# SCHEMATIC_INKTIME.net
KiCad netlist of a schematic drawn in EAGLE
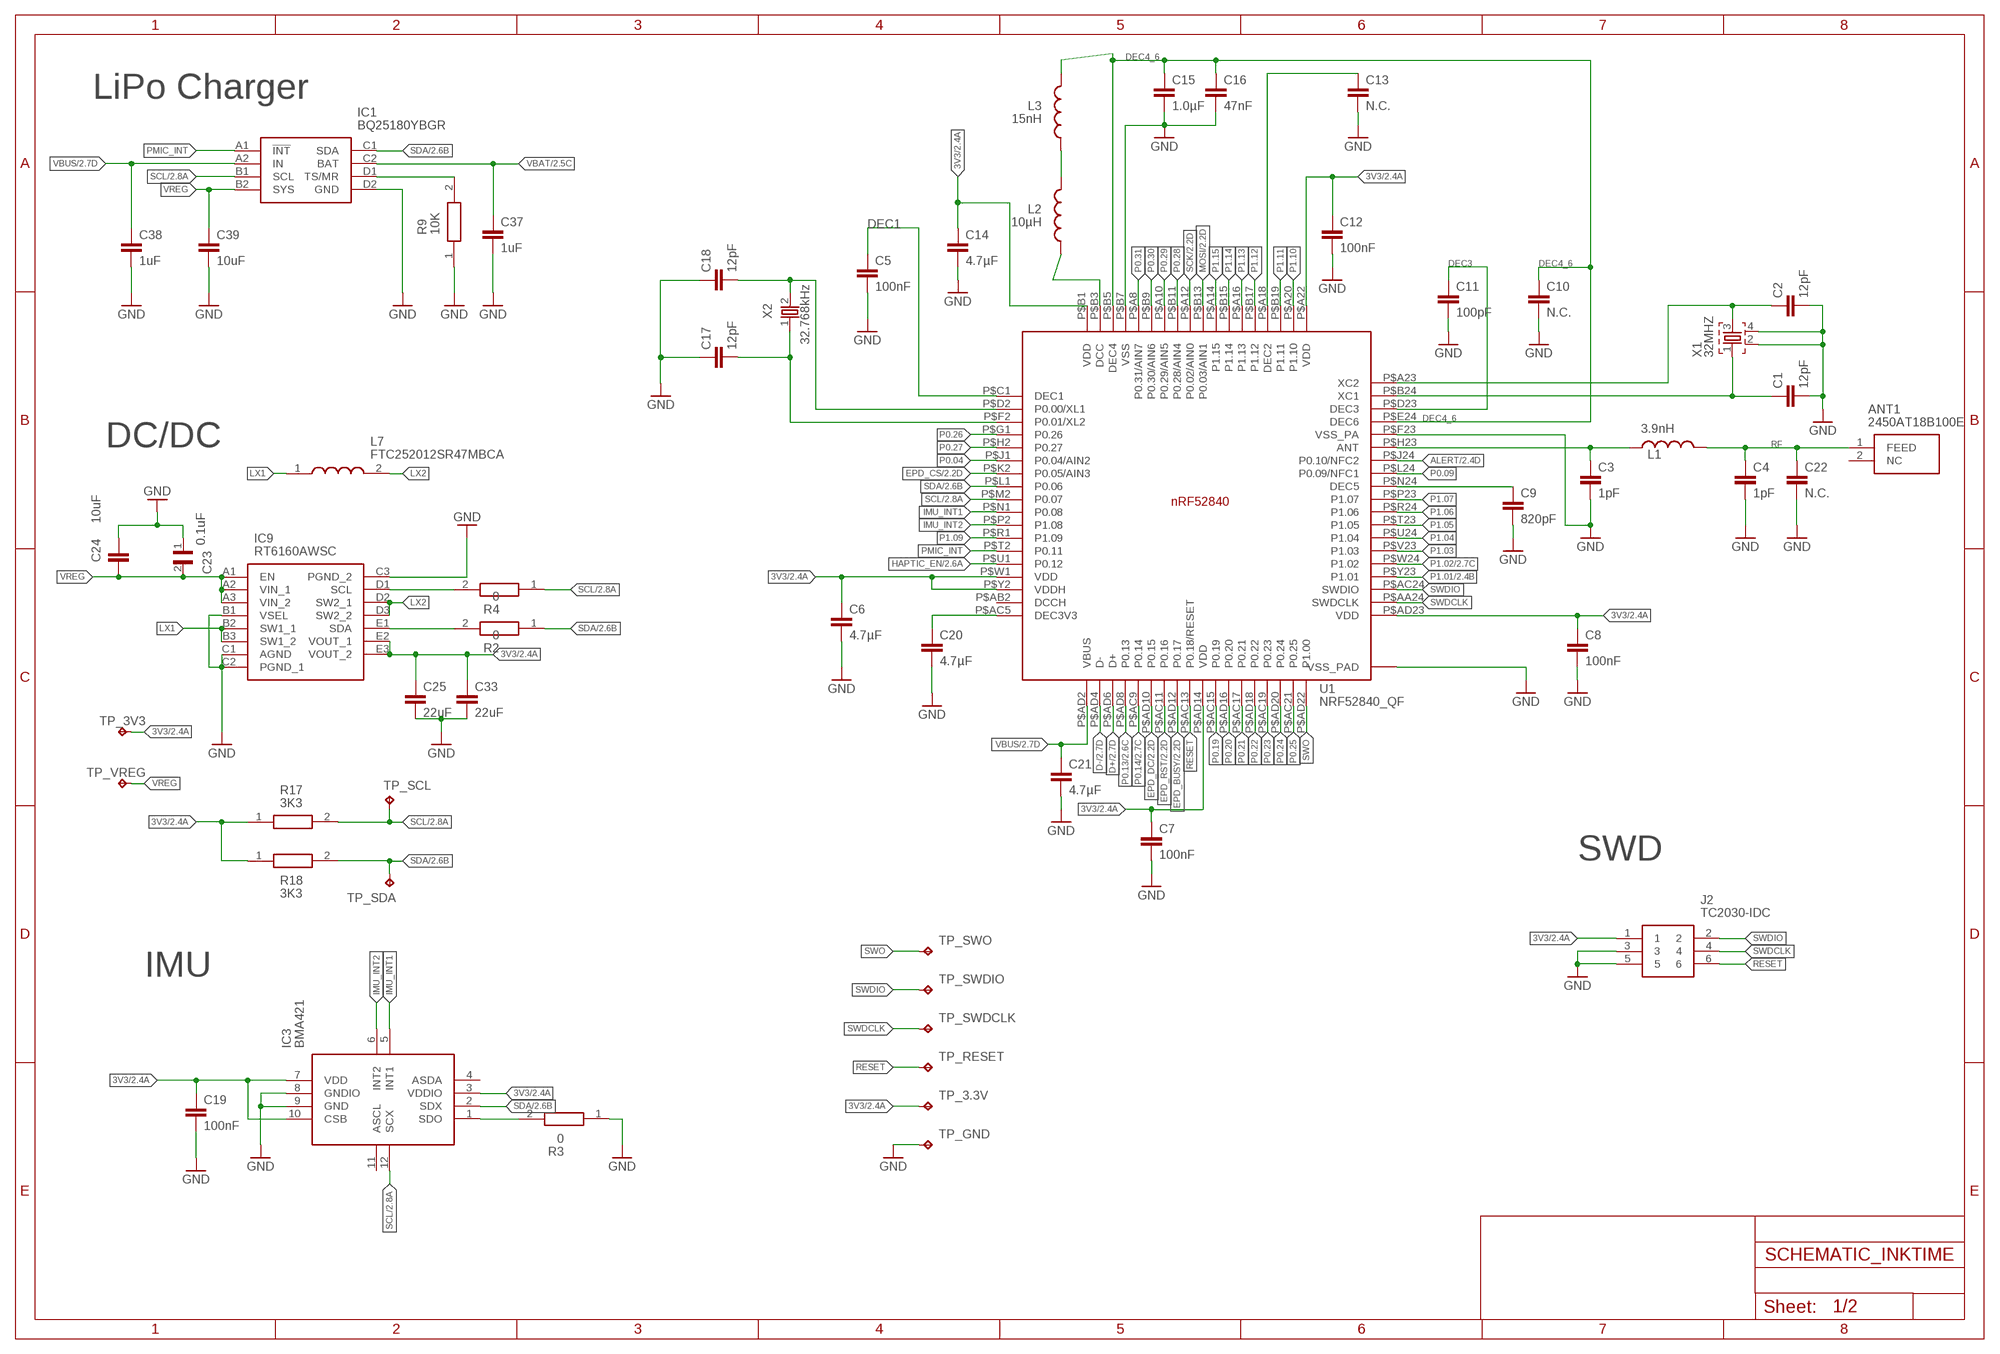
[diagram p0: schematic, sheet 1]
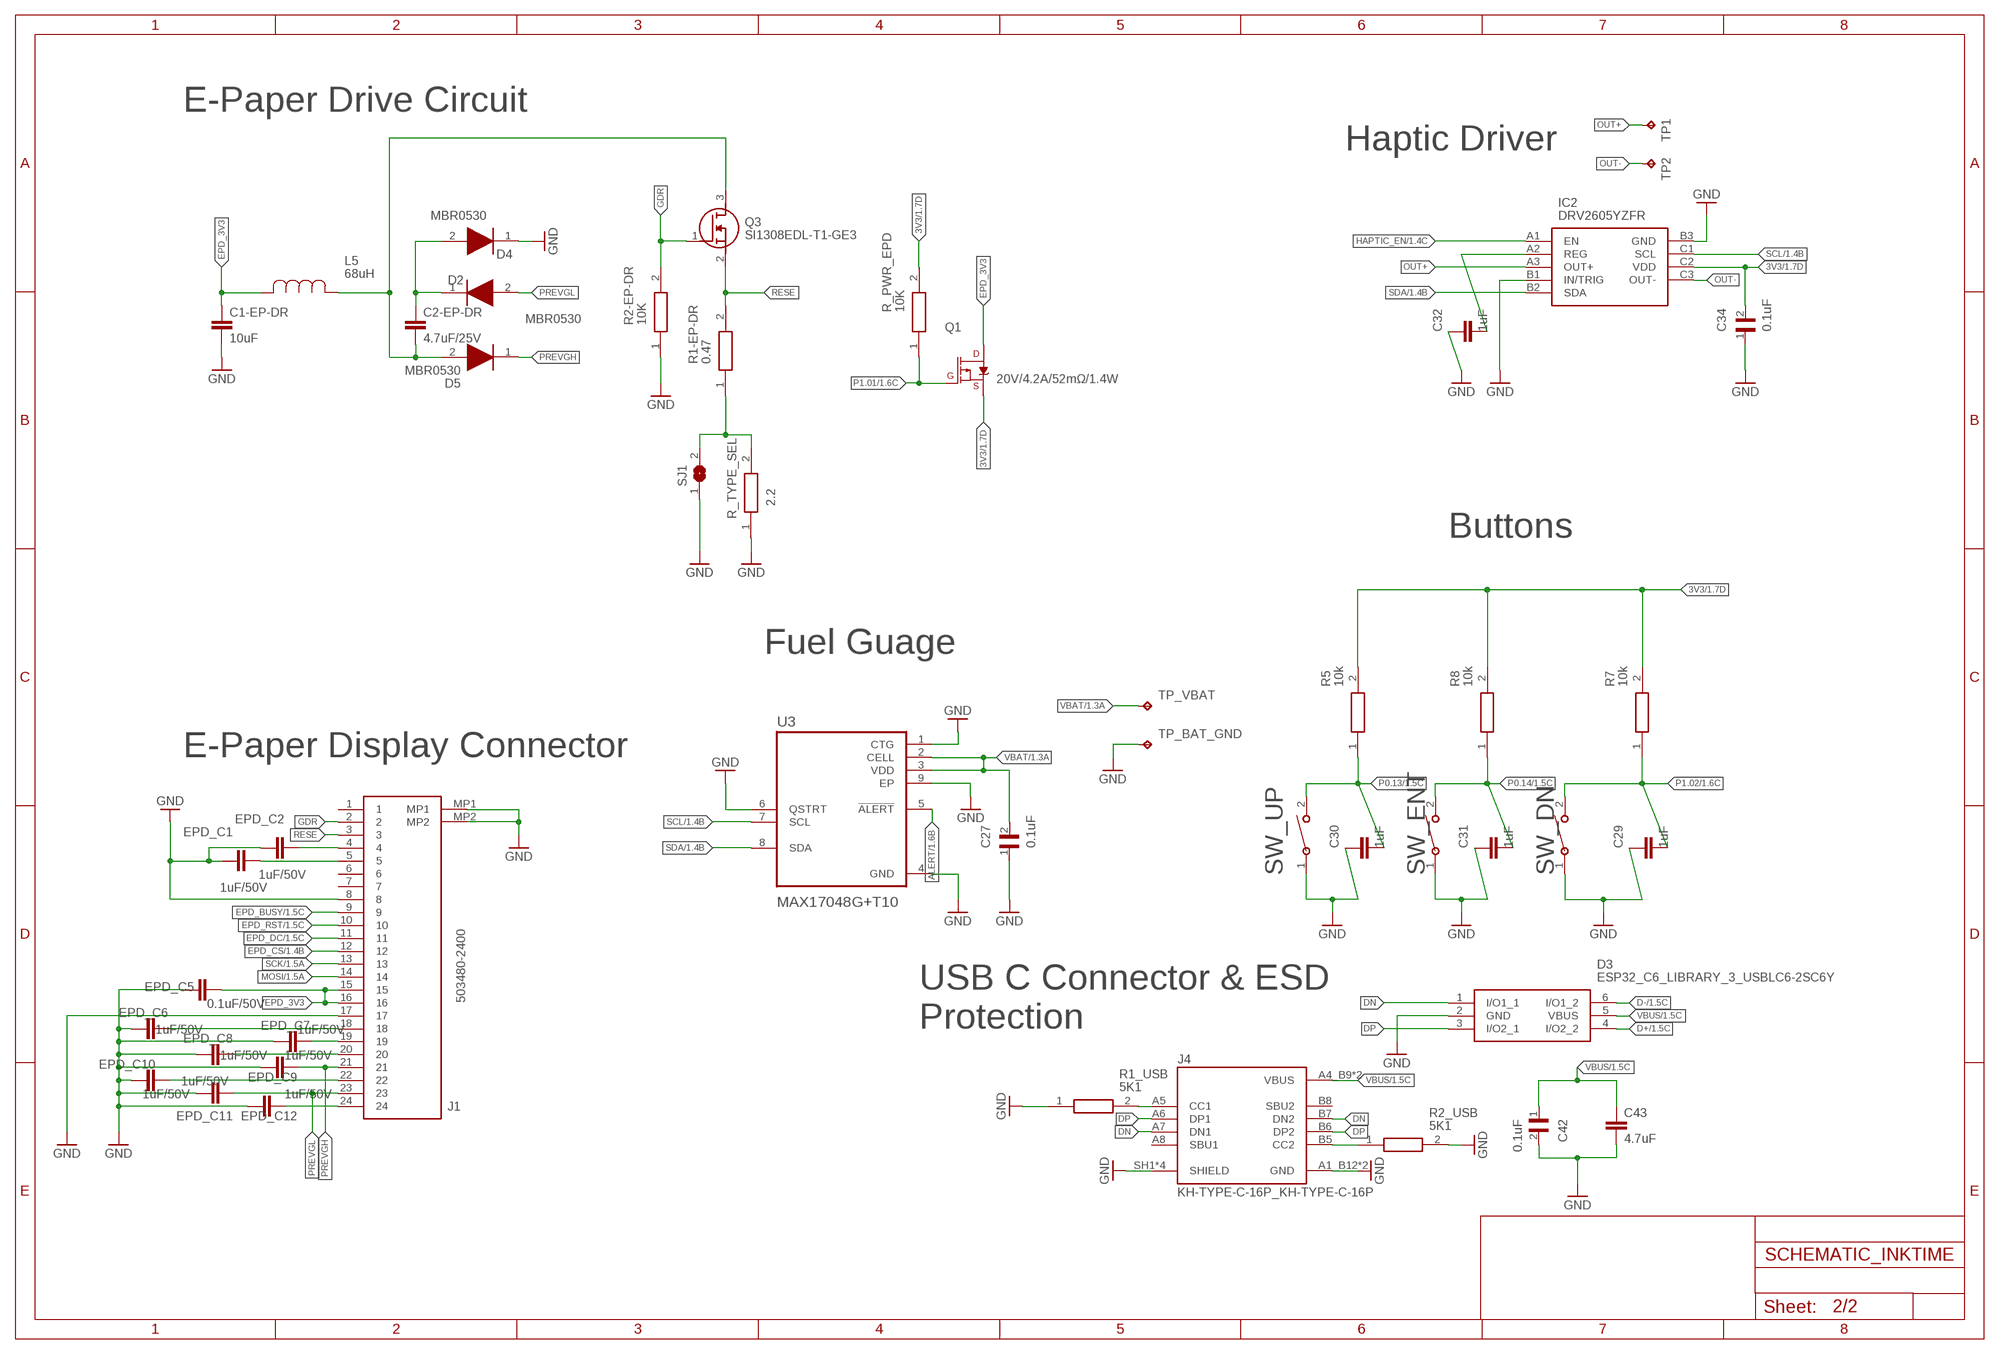
[diagram p1: schematic, sheet 2]

(export (version "E")
  (design (tool "Eeschema 10.0.6"))
  (components
    (comp (ref "ANT1")
      (value "2450AT18B100E")
      (footprint "eagle-import:2450AT18B100E_ANTC3216X140N")
      (fields (field (name "MOUSER_PART_NUMBER") "609-2450AT18B100E"))
      (libsource (lib "eagle-import") (part "2450AT18B100E_2450AT18B100E"))
    )
    (comp (ref "C1")
      (value "12pF")
      (footprint "eagle-import:NORDIC_NRF_3_RESC0201_L")
      (libsource (lib "eagle-import") (part "NORDIC_NRF_3_CAPACITOR_0201_L"))
    )
    (comp (ref "C2")
      (value "12pF")
      (footprint "eagle-import:NORDIC_NRF_3_RESC0201_L")
      (libsource (lib "eagle-import") (part "NORDIC_NRF_3_CAPACITOR_0201_L"))
    )
    (comp (ref "C3")
      (value "1pF")
      (footprint "eagle-import:NORDIC_NRF_3_RESC0201_L")
      (libsource (lib "eagle-import") (part "NORDIC_NRF_3_CAPACITOR_0201_L"))
    )
    (comp (ref "C4")
      (value "1pF")
      (footprint "eagle-import:NORDIC_NRF_3_RESC0201_L")
      (libsource (lib "eagle-import") (part "NORDIC_NRF_3_CAPACITOR_0201_L"))
    )
    (comp (ref "C5")
      (value "100nF")
      (footprint "eagle-import:NORDIC_NRF_3_RESC0201_L")
      (libsource (lib "eagle-import") (part "NORDIC_NRF_3_CAPACITOR_0201_L"))
    )
    (comp (ref "C6")
      (value "4.7µF")
      (footprint "eagle-import:NORDIC_NRF_3_RESC0402_L")
      (libsource (lib "eagle-import") (part "NORDIC_NRF_3_CAPACITOR_0402_L"))
    )
    (comp (ref "C7")
      (value "100nF")
      (footprint "eagle-import:NORDIC_NRF_3_RESC0201_L")
      (libsource (lib "eagle-import") (part "NORDIC_NRF_3_CAPACITOR_0201_L"))
    )
    (comp (ref "C8")
      (value "100nF")
      (footprint "eagle-import:NORDIC_NRF_3_RESC0201_L")
      (libsource (lib "eagle-import") (part "NORDIC_NRF_3_CAPACITOR_0201_L"))
    )
    (comp (ref "C9")
      (value "820pF")
      (footprint "eagle-import:NORDIC_NRF_3_RESC0201_L")
      (libsource (lib "eagle-import") (part "NORDIC_NRF_3_CAPACITOR_0201_L"))
    )
    (comp (ref "C10")
      (value "N.C.")
      (footprint "eagle-import:NORDIC_NRF_3_RESC0201_L")
      (libsource (lib "eagle-import") (part "NORDIC_NRF_3_CAPACITOR_0201_L"))
    )
    (comp (ref "C11")
      (value "100pF")
      (footprint "eagle-import:NORDIC_NRF_3_RESC0201_L")
      (libsource (lib "eagle-import") (part "NORDIC_NRF_3_CAPACITOR_0201_L"))
    )
    (comp (ref "C12")
      (value "100nF")
      (footprint "eagle-import:NORDIC_NRF_3_RESC0201_L")
      (libsource (lib "eagle-import") (part "NORDIC_NRF_3_CAPACITOR_0201_L"))
    )
    (comp (ref "C13")
      (value "N.C.")
      (footprint "eagle-import:NORDIC_NRF_3_RESC0201_L")
      (libsource (lib "eagle-import") (part "NORDIC_NRF_3_CAPACITOR_0201_L"))
    )
    (comp (ref "C14")
      (value "4.7µF")
      (footprint "eagle-import:NORDIC_NRF_3_RESC0402_L")
      (libsource (lib "eagle-import") (part "NORDIC_NRF_3_CAPACITOR_0402_L"))
    )
    (comp (ref "C15")
      (value "1.0µF")
      (footprint "eagle-import:NORDIC_NRF_3_RESC0402_L")
      (libsource (lib "eagle-import") (part "NORDIC_NRF_3_CAPACITOR_0402_L"))
    )
    (comp (ref "C16")
      (value "47nF")
      (footprint "eagle-import:NORDIC_NRF_3_RESC0201_L")
      (libsource (lib "eagle-import") (part "NORDIC_NRF_3_CAPACITOR_0201_L"))
    )
    (comp (ref "C17")
      (value "12pF")
      (footprint "eagle-import:NORDIC_NRF_3_RESC0201_L")
      (libsource (lib "eagle-import") (part "NORDIC_NRF_3_CAPACITOR_0201_L"))
    )
    (comp (ref "C18")
      (value "12pF")
      (footprint "eagle-import:NORDIC_NRF_3_RESC0201_L")
      (libsource (lib "eagle-import") (part "NORDIC_NRF_3_CAPACITOR_0201_L"))
    )
    (comp (ref "C19")
      (value "100nF")
      (footprint "eagle-import:NORDIC_NRF_3_RESC0201_L")
      (libsource (lib "eagle-import") (part "NORDIC_NRF_3_CAPACITOR_0201_L"))
    )
    (comp (ref "C20")
      (value "4.7µF")
      (footprint "eagle-import:NORDIC_NRF_3_RESC0402_L")
      (libsource (lib "eagle-import") (part "NORDIC_NRF_3_CAPACITOR_0402_L"))
    )
    (comp (ref "C21")
      (value "4.7µF")
      (footprint "eagle-import:NORDIC_NRF_3_RESC0402_L")
      (libsource (lib "eagle-import") (part "NORDIC_NRF_3_CAPACITOR_0402_L"))
    )
    (comp (ref "C22")
      (value "N.C.")
      (footprint "eagle-import:NORDIC_NRF_3_RESC0201_L")
      (libsource (lib "eagle-import") (part "NORDIC_NRF_3_CAPACITOR_0201_L"))
    )
    (comp (ref "C23")
      (value "0.1uF")
      (footprint "eagle-import:GRM011R60J152KE01L_2_CAPC0201X13N")
      (fields (field (name "MF") "Murata") (field (name "MP") "GRM011R60J152KE01L"))
      (libsource (lib "eagle-import") (part "GRM011R60J152KE01L_2_GRM011R60J152KE01L"))
    )
    (comp (ref "C24")
      (value "10uF")
      (footprint "eagle-import:NORDIC_NRF_3_RESC0402_L")
      (libsource (lib "eagle-import") (part "NORDIC_NRF_3_CAPACITOR_0402_L"))
    )
    (comp (ref "C25")
      (value "22uF")
      (footprint "eagle-import:NORDIC_NRF_3_RESC0402_L")
      (libsource (lib "eagle-import") (part "NORDIC_NRF_3_CAPACITOR_0402_L"))
    )
    (comp (ref "C33")
      (value "22uF")
      (footprint "eagle-import:NORDIC_NRF_3_RESC0402_L")
      (libsource (lib "eagle-import") (part "NORDIC_NRF_3_CAPACITOR_0402_L"))
    )
    (comp (ref "C37")
      (value "1uF")
      (footprint "eagle-import:NORDIC_NRF_3_RESC0402_L")
      (libsource (lib "eagle-import") (part "NORDIC_NRF_3_CAPACITOR_0402_L"))
    )
    (comp (ref "C38")
      (value "1uF")
      (footprint "eagle-import:NORDIC_NRF_3_RESC0402_L")
      (libsource (lib "eagle-import") (part "NORDIC_NRF_3_CAPACITOR_0402_L"))
    )
    (comp (ref "C39")
      (value "10uF")
      (footprint "eagle-import:NORDIC_NRF_3_RESC0402_L")
      (libsource (lib "eagle-import") (part "NORDIC_NRF_3_CAPACITOR_0402_L"))
    )
    (comp (ref "IC1")
      (value "BQ25180YBGR")
      (footprint "eagle-import:BQ25180YBGR_BGA8C40P2X4_100X155X50")
      (fields (field (name "MOUSER_PART_NUMBER") "595-BQ25180YBGR"))
      (libsource (lib "eagle-import") (part "BQ25180YBGR_BQ25180YBGR"))
    )
    (comp (ref "IC3")
      (value "BMA421")
      (footprint "eagle-import:BMA423_BMA423")
      (fields (field (name "ARROW_PART_NUMBER") "BMA423") (field (name "MOUSER_PART_NUMBER") "262-BMA423"))
      (libsource (lib "eagle-import") (part "BMA423_BMA423"))
    )
    (comp (ref "IC9")
      (value "RT6160AWSC")
      (footprint "eagle-import:RT6160AWSC_BGA15C40P3X5_140X230X60")
      (fields (field (name "MOUSER_PART_NUMBER") "835-RT6160AWSC"))
      (libsource (lib "eagle-import") (part "RT6160AWSC_RT6160AWSC"))
    )
    (comp (ref "J2")
      (value "TC2030-IDC")
      (footprint "eagle-import:TC2030-IDC_TC2030IDC")
      (libsource (lib "eagle-import") (part "TC2030-IDC_TC2030-IDC"))
    )
    (comp (ref "L1")
      (value "3.9nH")
      (footprint "eagle-import:NORDIC_NRF_2_RESC0402_L")
      (libsource (lib "eagle-import") (part "NORDIC_NRF_2_INDUCTOR_0402_L"))
    )
    (comp (ref "L2")
      (value "10µH")
      (footprint "eagle-import:NORDIC_NRF_2_RESC0402_L")
      (libsource (lib "eagle-import") (part "NORDIC_NRF_2_INDUCTOR_0402_L"))
    )
    (comp (ref "L3")
      (value "15nH")
      (footprint "eagle-import:NORDIC_NRF_2_RESC0402_L")
      (libsource (lib "eagle-import") (part "NORDIC_NRF_2_INDUCTOR_0402_L"))
    )
    (comp (ref "L7")
      (value "FTC252012SR47MBCA")
      (footprint "eagle-import:MLP2016SR47MT0S1_INDC2016X100N")
      (libsource (lib "eagle-import") (part "MLP2016SR47MT0S1_FTC252012SR47MBCA"))
    )
    (comp (ref "R2")
      (value "0")
      (footprint "eagle-import:CPF0201D7K68C1_0201")
      (libsource (lib "eagle-import") (part "CPF0201D7K68C1_CPF0201D7K68C1"))
    )
    (comp (ref "R3")
      (value "0")
      (footprint "eagle-import:CPF0201D7K68C1_0201")
      (libsource (lib "eagle-import") (part "CPF0201D7K68C1_CPF0201D7K68C1"))
    )
    (comp (ref "R4")
      (value "0")
      (footprint "eagle-import:CPF0201D7K68C1_0201")
      (libsource (lib "eagle-import") (part "CPF0201D7K68C1_CPF0201D7K68C1"))
    )
    (comp (ref "R9")
      (value "10K")
      (footprint "eagle-import:CPF0201D7K68C1_0201")
      (libsource (lib "eagle-import") (part "CPF0201D7K68C1_CPF0201D7K68C1"))
    )
    (comp (ref "R17")
      (value "3K3")
      (footprint "eagle-import:CPF0201D7K68C1_0201")
      (libsource (lib "eagle-import") (part "CPF0201D7K68C1_CPF0201D7K68C1"))
    )
    (comp (ref "R18")
      (value "3K3")
      (footprint "eagle-import:CPF0201D7K68C1_0201")
      (libsource (lib "eagle-import") (part "CPF0201D7K68C1_CPF0201D7K68C1"))
    )
    (comp (ref "TP_3.3V")
      (value "HECTOR_WATCH_1_TPTP20R")
      (footprint "eagle-import:HECTOR_WATCH_1_TP20R")
      (libsource (lib "eagle-import") (part "HECTOR_WATCH_1_TPTP20R"))
    )
    (comp (ref "TP_3V3")
      (value "HECTOR_WATCH_1_TPTP20R")
      (footprint "eagle-import:HECTOR_WATCH_1_TP20R")
      (libsource (lib "eagle-import") (part "HECTOR_WATCH_1_TPTP20R"))
    )
    (comp (ref "TP_GND")
      (value "HECTOR_WATCH_1_TPTP20R")
      (footprint "eagle-import:HECTOR_WATCH_1_TP20R")
      (libsource (lib "eagle-import") (part "HECTOR_WATCH_1_TPTP20R"))
    )
    (comp (ref "TP_RESET")
      (value "HECTOR_WATCH_1_TPTP20R")
      (footprint "eagle-import:HECTOR_WATCH_1_TP20R")
      (libsource (lib "eagle-import") (part "HECTOR_WATCH_1_TPTP20R"))
    )
    (comp (ref "TP_SCL")
      (value "HECTOR_WATCH_1_TPTP20R")
      (footprint "eagle-import:HECTOR_WATCH_1_TP20R")
      (libsource (lib "eagle-import") (part "HECTOR_WATCH_1_TPTP20R"))
    )
    (comp (ref "TP_SDA")
      (value "HECTOR_WATCH_1_TPTP20R")
      (footprint "eagle-import:HECTOR_WATCH_1_TP20R")
      (libsource (lib "eagle-import") (part "HECTOR_WATCH_1_TPTP20R"))
    )
    (comp (ref "TP_SWDCLK")
      (value "HECTOR_WATCH_1_TPTP20R")
      (footprint "eagle-import:HECTOR_WATCH_1_TP20R")
      (libsource (lib "eagle-import") (part "HECTOR_WATCH_1_TPTP20R"))
    )
    (comp (ref "TP_SWDIO")
      (value "HECTOR_WATCH_1_TPTP20R")
      (footprint "eagle-import:HECTOR_WATCH_1_TP20R")
      (libsource (lib "eagle-import") (part "HECTOR_WATCH_1_TPTP20R"))
    )
    (comp (ref "TP_SWO")
      (value "HECTOR_WATCH_1_TPTP20R")
      (footprint "eagle-import:HECTOR_WATCH_1_TP20R")
      (libsource (lib "eagle-import") (part "HECTOR_WATCH_1_TPTP20R"))
    )
    (comp (ref "TP_VREG")
      (value "HECTOR_WATCH_1_TPTP20R")
      (footprint "eagle-import:HECTOR_WATCH_1_TP20R")
      (libsource (lib "eagle-import") (part "HECTOR_WATCH_1_TPTP20R"))
    )
    (comp (ref "U1")
      (value "NRF52840_QF")
      (footprint "eagle-import:NORDIC_NRF_4_AQFN50P700X700X85_HS-74N")
      (libsource (lib "eagle-import") (part "NORDIC_NRF_4_NRF52840_QF"))
    )
    (comp (ref "X1")
      (value "32MHZ")
      (footprint "eagle-import:NORDIC_NRF_BT-XTAL_2016_N")
      (libsource (lib "eagle-import") (part "NORDIC_NRF_XTAL_32MHZ"))
    )
    (comp (ref "X2")
      (value "32.768kHz")
      (footprint "eagle-import:NORDIC_NRF_1_XTAL_3215_N")
      (libsource (lib "eagle-import") (part "NORDIC_NRF_1_XTAL_32KHZ"))
    )
    (comp (ref "C1-EP-DR")
      (value "10uF")
      (footprint "eagle-import:NORDIC_NRF_3_RESC0402_L")
      (libsource (lib "eagle-import") (part "NORDIC_NRF_3_CAPACITOR_0402_L"))
    )
    (comp (ref "C2-EP-DR")
      (value "4.7uF/25V")
      (footprint "eagle-import:NORDIC_NRF_3_RESC0402_L")
      (libsource (lib "eagle-import") (part "NORDIC_NRF_3_CAPACITOR_0402_L"))
    )
    (comp (ref "C27")
      (value "0.1uF")
      (footprint "eagle-import:GRM011R60J152KE01L_2_CAPC0201X13N")
      (fields (field (name "MF") "Murata") (field (name "MP") "GRM011R60J152KE01L"))
      (libsource (lib "eagle-import") (part "GRM011R60J152KE01L_2_GRM011R60J152KE01L"))
    )
    (comp (ref "C29")
      (value "1uF")
      (footprint "eagle-import:NORDIC_NRF_3_RESC0402_L")
      (libsource (lib "eagle-import") (part "NORDIC_NRF_3_CAPACITOR_0402_L"))
    )
    (comp (ref "C30")
      (value "1uF")
      (footprint "eagle-import:NORDIC_NRF_3_RESC0402_L")
      (libsource (lib "eagle-import") (part "NORDIC_NRF_3_CAPACITOR_0402_L"))
    )
    (comp (ref "C31")
      (value "1uF")
      (footprint "eagle-import:NORDIC_NRF_3_RESC0402_L")
      (libsource (lib "eagle-import") (part "NORDIC_NRF_3_CAPACITOR_0402_L"))
    )
    (comp (ref "C32")
      (value "1uF")
      (footprint "eagle-import:NORDIC_NRF_3_RESC0402_L")
      (libsource (lib "eagle-import") (part "NORDIC_NRF_3_CAPACITOR_0402_L"))
    )
    (comp (ref "C34")
      (value "0.1uF")
      (footprint "eagle-import:GRM011R60J152KE01L_2_CAPC0201X13N")
      (fields (field (name "MF") "Murata") (field (name "MP") "GRM011R60J152KE01L"))
      (libsource (lib "eagle-import") (part "GRM011R60J152KE01L_2_GRM011R60J152KE01L"))
    )
    (comp (ref "C42")
      (value "0.1uF")
      (footprint "eagle-import:GRM011R60J152KE01L_2_CAPC0201X13N")
      (fields (field (name "MF") "Murata") (field (name "MP") "GRM011R60J152KE01L"))
      (libsource (lib "eagle-import") (part "GRM011R60J152KE01L_2_GRM011R60J152KE01L"))
    )
    (comp (ref "C43")
      (value "4.7uF")
      (footprint "eagle-import:NORDIC_NRF_3_RESC0402_L")
      (libsource (lib "eagle-import") (part "NORDIC_NRF_3_CAPACITOR_0402_L"))
    )
    (comp (ref "D2")
      (value "MBR0530")
      (footprint "eagle-import:ESP32_C6_LIBRARY_5_SOD3716X135N")
      (fields (field (name "MF") "ON Semiconductor"))
      (libsource (lib "eagle-import") (part "ESP32_C6_LIBRARY_5_MBR0530"))
    )
    (comp (ref "D3")
      (value "ESP32_C6_LIBRARY_3_USBLC6-2SC6Y")
      (footprint "eagle-import:ESP32_C6_LIBRARY_3_SOT95P280X145-6N")
      (fields (field (name "MF") "STMicroelectronics") (field (name "MP") "USBLC6-2SC6Y"))
      (libsource (lib "eagle-import") (part "ESP32_C6_LIBRARY_3_USBLC6-2SC6Y"))
    )
    (comp (ref "D4")
      (value "MBR0530")
      (footprint "eagle-import:ESP32_C6_LIBRARY_5_SOD3716X135N")
      (fields (field (name "MF") "ON Semiconductor"))
      (libsource (lib "eagle-import") (part "ESP32_C6_LIBRARY_5_MBR0530"))
    )
    (comp (ref "D5")
      (value "MBR0530")
      (footprint "eagle-import:ESP32_C6_LIBRARY_5_SOD3716X135N")
      (fields (field (name "MF") "ON Semiconductor"))
      (libsource (lib "eagle-import") (part "ESP32_C6_LIBRARY_5_MBR0530"))
    )
    (comp (ref "EPD_C1")
      (value "1uF/50V")
      (footprint "eagle-import:NORDIC_NRF_3_RESC0402_L")
      (libsource (lib "eagle-import") (part "NORDIC_NRF_3_CAPACITOR_0402_L"))
    )
    (comp (ref "EPD_C2")
      (value "1uF/50V")
      (footprint "eagle-import:NORDIC_NRF_3_RESC0402_L")
      (libsource (lib "eagle-import") (part "NORDIC_NRF_3_CAPACITOR_0402_L"))
    )
    (comp (ref "EPD_C5")
      (value "0.1uF/50V")
      (footprint "eagle-import:NORDIC_NRF_3_RESC0201_L")
      (libsource (lib "eagle-import") (part "NORDIC_NRF_3_CAPACITOR_0201_L"))
    )
    (comp (ref "EPD_C6")
      (value "1uF/50V")
      (footprint "eagle-import:NORDIC_NRF_3_RESC0402_L")
      (libsource (lib "eagle-import") (part "NORDIC_NRF_3_CAPACITOR_0402_L"))
    )
    (comp (ref "EPD_C7")
      (value "1uF/50V")
      (footprint "eagle-import:NORDIC_NRF_3_RESC0402_L")
      (libsource (lib "eagle-import") (part "NORDIC_NRF_3_CAPACITOR_0402_L"))
    )
    (comp (ref "EPD_C8")
      (value "1uF/50V")
      (footprint "eagle-import:NORDIC_NRF_3_RESC0402_L")
      (libsource (lib "eagle-import") (part "NORDIC_NRF_3_CAPACITOR_0402_L"))
    )
    (comp (ref "EPD_C9")
      (value "1uF/50V")
      (footprint "eagle-import:NORDIC_NRF_3_RESC0402_L")
      (libsource (lib "eagle-import") (part "NORDIC_NRF_3_CAPACITOR_0402_L"))
    )
    (comp (ref "EPD_C10")
      (value "1uF/50V")
      (footprint "eagle-import:NORDIC_NRF_3_RESC0402_L")
      (libsource (lib "eagle-import") (part "NORDIC_NRF_3_CAPACITOR_0402_L"))
    )
    (comp (ref "EPD_C11")
      (value "1uF/50V")
      (footprint "eagle-import:NORDIC_NRF_3_RESC0402_L")
      (libsource (lib "eagle-import") (part "NORDIC_NRF_3_CAPACITOR_0402_L"))
    )
    (comp (ref "EPD_C12")
      (value "1uF/50V")
      (footprint "eagle-import:NORDIC_NRF_3_RESC0402_L")
      (libsource (lib "eagle-import") (part "NORDIC_NRF_3_CAPACITOR_0402_L"))
    )
    (comp (ref "IC2")
      (value "DRV2605YZFR")
      (footprint "eagle-import:DRV2605YZFR_BGA9C50P3X3_144X144X62")
      (libsource (lib "eagle-import") (part "DRV2605YZFR_DRV2605YZFR"))
    )
    (comp (ref "J1")
      (value "503480-2400")
      (footprint "eagle-import:503480-2400_5034802400")
      (fields (field (name "MOUSER_PART_NUMBER") "538-503480-2400"))
      (libsource (lib "eagle-import") (part "503480-2400_503480-2400"))
    )
    (comp (ref "J4")
      (value "KH-TYPE-C-16P_KH-TYPE-C-16P")
      (footprint "eagle-import:KH-TYPE-C-16P_KINGHELM_KH-TYPE-C-16P")
      (fields (field (name "MF") "kinghelm") (field (name "MP") "KH-TYPE-C-16P"))
      (libsource (lib "eagle-import") (part "KH-TYPE-C-16P_KH-TYPE-C-16P"))
    )
    (comp (ref "L5")
      (value "68uH")
      (footprint "eagle-import:ESP32_C6_LIBRARY_2_IND_4828-WE-TPC_WRE")
      (fields
        (field (name "MANUFACTURER_PART_NUMBER") "744043680")
        (field (name "COPYRIGHT") "Copyright (C) 2024 Ultra Librarian. All rights reserved.")
      )
      (libsource (lib "eagle-import") (part "ESP32_C6_LIBRARY_2_744043680IND_4828-WE-TPC_WRE"))
    )
    (comp (ref "Q1")
      (value "20V/4.2A/52mΩ/1.4W")
      (footprint "eagle-import:ESP32_C6_LIBRARY_4_ESP32_C6_LIBRARY_4_ESP32_C6_LIBRARY_4_ESP32_C6_LIBRARY_4_ESP32_WROVER_SPARKFUN-DISCRETESEMI_SOT23-3")
      (libsource (lib "eagle-import") (part "ESP32_C6_LIBRARY_4_ESP32_WROVER_SPARKFUN-DISCRETESEMI_MOSFET_PCH-DMG2305UX-7"))
    )
    (comp (ref "Q3")
      (value "SI1308EDL-T1-GE3")
      (footprint "eagle-import:ESP32_C6_LIBRARY_6_SOT65P210X110-3N")
      (fields (field (name "MF") "Vishay Siliconix"))
      (libsource (lib "eagle-import") (part "ESP32_C6_LIBRARY_6_SI1308EDL-T1-GE3"))
    )
    (comp (ref "R1-EP-DR")
      (value "0.47")
      (footprint "eagle-import:CPF0201D7K68C1_0201")
      (libsource (lib "eagle-import") (part "CPF0201D7K68C1_CPF0201D7K68C1"))
    )
    (comp (ref "R1_USB")
      (value "5K1")
      (footprint "eagle-import:CPF0201D7K68C1_0201")
      (libsource (lib "eagle-import") (part "CPF0201D7K68C1_CPF0201D7K68C1"))
    )
    (comp (ref "R2-EP-DR")
      (value "10K")
      (footprint "eagle-import:CPF0201D7K68C1_0201")
      (libsource (lib "eagle-import") (part "CPF0201D7K68C1_CPF0201D7K68C1"))
    )
    (comp (ref "R2_USB")
      (value "5K1")
      (footprint "eagle-import:CPF0201D7K68C1_0201")
      (libsource (lib "eagle-import") (part "CPF0201D7K68C1_CPF0201D7K68C1"))
    )
    (comp (ref "R5")
      (value "10k")
      (footprint "eagle-import:CPF0201D7K68C1_0201")
      (libsource (lib "eagle-import") (part "CPF0201D7K68C1_CPF0201D7K68C1"))
    )
    (comp (ref "R7")
      (value "10k")
      (footprint "eagle-import:CPF0201D7K68C1_0201")
      (libsource (lib "eagle-import") (part "CPF0201D7K68C1_CPF0201D7K68C1"))
    )
    (comp (ref "R8")
      (value "10k")
      (footprint "eagle-import:CPF0201D7K68C1_0201")
      (libsource (lib "eagle-import") (part "CPF0201D7K68C1_CPF0201D7K68C1"))
    )
    (comp (ref "R_PWR_EPD")
      (value "10K")
      (footprint "eagle-import:CPF0201D7K68C1_0201")
      (libsource (lib "eagle-import") (part "CPF0201D7K68C1_CPF0201D7K68C1"))
    )
    (comp (ref "R_TYPE_SEL")
      (value "2.2")
      (footprint "eagle-import:CPF0201D7K68C1_0201")
      (libsource (lib "eagle-import") (part "CPF0201D7K68C1_CPF0201D7K68C1"))
    )
    (comp (ref "SJ1")
      (value "ESP32_C6_LIBRARY_7_JUMPER_SJ")
      (footprint "eagle-import:ESP32_C6_LIBRARY_7_JUMPER_SJ")
      (libsource (lib "eagle-import") (part "ESP32_C6_LIBRARY_7_JUMPER_SJ"))
    )
    (comp (ref "SW_DN")
      (value "2025-10-22_07-23-44_LIBRARY_EVP-AKE31ASW_EVP-AKE31A_PAN")
      (footprint "eagle-import:2025-10-22_07-23-44_LIBRARY_SW_EVP-AKE31A_PAN")
      (fields
        (field (name "MANUFACTURER_PART_NUMBER") "EVP-AKE31A")
        (field (name "COPYRIGHT") "Copyright (C) 2025 Ultra Librarian. All rights reserved.")
      )
      (libsource (lib "eagle-import") (part "2025-10-22_07-23-44_LIBRARY_EVP-AKE31ASW_EVP-AKE31A_PAN"))
    )
    (comp (ref "SW_ENT")
      (value "2025-10-22_07-23-44_LIBRARY_EVP-AKE31ASW_EVP-AKE31A_PAN")
      (footprint "eagle-import:2025-10-22_07-23-44_LIBRARY_SW_EVP-AKE31A_PAN")
      (fields
        (field (name "MANUFACTURER_PART_NUMBER") "EVP-AKE31A")
        (field (name "COPYRIGHT") "Copyright (C) 2025 Ultra Librarian. All rights reserved.")
      )
      (libsource (lib "eagle-import") (part "2025-10-22_07-23-44_LIBRARY_EVP-AKE31ASW_EVP-AKE31A_PAN"))
    )
    (comp (ref "SW_UP")
      (value "2025-10-22_07-23-44_LIBRARY_EVP-AKE31ASW_EVP-AKE31A_PAN")
      (footprint "eagle-import:2025-10-22_07-23-44_LIBRARY_SW_EVP-AKE31A_PAN")
      (fields
        (field (name "MANUFACTURER_PART_NUMBER") "EVP-AKE31A")
        (field (name "COPYRIGHT") "Copyright (C) 2025 Ultra Librarian. All rights reserved.")
      )
      (libsource (lib "eagle-import") (part "2025-10-22_07-23-44_LIBRARY_EVP-AKE31ASW_EVP-AKE31A_PAN"))
    )
    (comp (ref "TP1")
      (value "HECTOR_WATCH_1_TPTP20R")
      (footprint "eagle-import:HECTOR_WATCH_1_TP20R")
      (libsource (lib "eagle-import") (part "HECTOR_WATCH_1_TPTP20R"))
    )
    (comp (ref "TP2")
      (value "HECTOR_WATCH_1_TPTP20R")
      (footprint "eagle-import:HECTOR_WATCH_1_TP20R")
      (libsource (lib "eagle-import") (part "HECTOR_WATCH_1_TPTP20R"))
    )
    (comp (ref "TP_BAT_GND")
      (value "HECTOR_WATCH_1_TPTP20R")
      (footprint "eagle-import:HECTOR_WATCH_1_TP20R")
      (libsource (lib "eagle-import") (part "HECTOR_WATCH_1_TPTP20R"))
    )
    (comp (ref "TP_VBAT")
      (value "HECTOR_WATCH_1_TPTP20R")
      (footprint "eagle-import:HECTOR_WATCH_1_TP20R")
      (libsource (lib "eagle-import") (part "HECTOR_WATCH_1_TPTP20R"))
    )
    (comp (ref "U3")
      (value "MAX17048G+T10")
      (footprint "eagle-import:ESP32_C6_LIBRARY_SON50P200X200X80-9N")
      (fields (field (name "MF") "Analog Devices"))
      (libsource (lib "eagle-import") (part "ESP32_C6_LIBRARY_MAX17048G+T10"))
    )
  )
  (nets
    (net (code "1") (name "3V3{slash}1.7D") (class "Default")
      (node (ref "C34") (pin "2") (pinfunction "2_2") (pintype "passive"))
      (node (ref "IC2") (pin "C2") (pinfunction "VDD_C2") (pintype "bidirectional"))
      (node (ref "Q1") (pin "2") (pinfunction "S_2") (pintype "bidirectional"))
      (node (ref "R5") (pin "2") (pinfunction "2_2") (pintype "bidirectional"))
      (node (ref "R7") (pin "2") (pinfunction "2_2") (pintype "bidirectional"))
      (node (ref "R8") (pin "2") (pinfunction "2_2") (pintype "bidirectional"))
      (node (ref "R_PWR_EPD") (pin "2") (pinfunction "2_2") (pintype "bidirectional"))
    )
    (net (code "2") (name "3V3{slash}2.4A") (class "Default")
      (node (ref "C12") (pin "1") (pinfunction "1_1") (pintype "passive"))
      (node (ref "C14") (pin "1") (pinfunction "1_1") (pintype "passive"))
      (node (ref "C19") (pin "1") (pinfunction "1_1") (pintype "passive"))
      (node (ref "C25") (pin "1") (pinfunction "1_1") (pintype "passive"))
      (node (ref "C33") (pin "1") (pinfunction "1_1") (pintype "passive"))
      (node (ref "C6") (pin "1") (pinfunction "1_1") (pintype "passive"))
      (node (ref "C7") (pin "1") (pinfunction "1_1") (pintype "passive"))
      (node (ref "C8") (pin "1") (pinfunction "1_1") (pintype "passive"))
      (node (ref "IC3") (pin "10") (pinfunction "CSB_10") (pintype "bidirectional"))
      (node (ref "IC3") (pin "3") (pinfunction "VDDIO_3") (pintype "bidirectional"))
      (node (ref "IC3") (pin "7") (pinfunction "VDD_7") (pintype "bidirectional"))
      (node (ref "IC9") (pin "E2") (pinfunction "VOUT_1_E2") (pintype "bidirectional"))
      (node (ref "IC9") (pin "E3") (pinfunction "VOUT_2_E3") (pintype "bidirectional"))
      (node (ref "J2") (pin "1") (pinfunction "1_1") (pintype "bidirectional"))
      (node (ref "R17") (pin "1") (pinfunction "1_1") (pintype "bidirectional"))
      (node (ref "R18") (pin "1") (pinfunction "1_1") (pintype "bidirectional"))
      (node (ref "TP_3.3V") (pin "TP") (pinfunction "TP_TP") (pintype "input"))
      (node (ref "TP_3V3") (pin "TP") (pinfunction "TP_TP") (pintype "input"))
      (node (ref "U1") (pin "P$A22") (pinfunction "VDD_P$A22") (pintype "power_in"))
      (node (ref "U1") (pin "P$AD14") (pinfunction "VDD_P$AD14") (pintype "power_in"))
      (node (ref "U1") (pin "P$AD23") (pinfunction "VDD_P$AD23") (pintype "power_in"))
      (node (ref "U1") (pin "P$B1") (pinfunction "VDD_P$B1") (pintype "power_in"))
      (node (ref "U1") (pin "P$W1") (pinfunction "VDD_P$W1") (pintype "power_in"))
      (node (ref "U1") (pin "P$Y2") (pinfunction "VDDH_P$Y2") (pintype "power_in"))
    )
    (net (code "3") (name "ALERT") (class "Default")
      (node (ref "U1") (pin "P$J24") (pinfunction "P0.10/NFC2_P$J24") (pintype "bidirectional"))
      (node (ref "U3") (pin "5") (pinfunction "~{ALERT}_5") (pintype "output"))
    )
    (net (code "4") (name "D+") (class "Default")
      (node (ref "D3") (pin "4") (pinfunction "I/O2_2_4") (pintype "bidirectional"))
      (node (ref "U1") (pin "P$AD6") (pinfunction "D+_P$AD6") (pintype "bidirectional"))
    )
    (net (code "5") (name "D-") (class "Default")
      (node (ref "D3") (pin "6") (pinfunction "I/O1_2_6") (pintype "bidirectional"))
      (node (ref "U1") (pin "P$AD4") (pinfunction "D-_P$AD4") (pintype "bidirectional"))
    )
    (net (code "6") (name "DEC1") (class "Default")
      (node (ref "C5") (pin "1") (pinfunction "1_1") (pintype "passive"))
      (node (ref "U1") (pin "P$C1") (pinfunction "DEC1_P$C1") (pintype "power_in"))
    )
    (net (code "7") (name "DEC3") (class "Default")
      (node (ref "C11") (pin "1") (pinfunction "1_1") (pintype "passive"))
      (node (ref "U1") (pin "P$D23") (pinfunction "DEC3_P$D23") (pintype "bidirectional"))
    )
    (net (code "8") (name "DEC4_6") (class "Default")
      (node (ref "C10") (pin "1") (pinfunction "1_1") (pintype "passive"))
      (node (ref "C15") (pin "1") (pinfunction "1_1") (pintype "passive"))
      (node (ref "C16") (pin "1") (pinfunction "1_1") (pintype "passive"))
      (node (ref "L3") (pin "2") (pinfunction "2_2") (pintype "passive"))
      (node (ref "U1") (pin "P$B5") (pinfunction "DEC4_P$B5") (pintype "power_in"))
      (node (ref "U1") (pin "P$E24") (pinfunction "DEC6_P$E24") (pintype "bidirectional"))
    )
    (net (code "9") (name "DN") (class "Default")
      (node (ref "D3") (pin "1") (pinfunction "I/O1_1_1") (pintype "bidirectional"))
      (node (ref "J4") (pin "A7") (pinfunction "DN1_A7") (pintype "bidirectional"))
      (node (ref "J4") (pin "B7") (pinfunction "DN2_B7") (pintype "bidirectional"))
    )
    (net (code "10") (name "DP") (class "Default")
      (node (ref "D3") (pin "3") (pinfunction "I/O2_1_3") (pintype "bidirectional"))
      (node (ref "J4") (pin "A6") (pinfunction "DP1_A6") (pintype "bidirectional"))
      (node (ref "J4") (pin "B6") (pinfunction "DP2_B6") (pintype "bidirectional"))
    )
    (net (code "11") (name "EPD_3V3") (class "Default")
      (node (ref "C1-EP-DR") (pin "1") (pinfunction "1_1") (pintype "passive"))
      (node (ref "EPD_C5") (pin "2") (pinfunction "2_2") (pintype "passive"))
      (node (ref "J1") (pin "15") (pinfunction "15_15") (pintype "bidirectional"))
      (node (ref "J1") (pin "16") (pinfunction "16_16") (pintype "bidirectional"))
      (node (ref "L5") (pin "2") (pinfunction "2_2") (pintype "passive"))
      (node (ref "Q1") (pin "3") (pinfunction "D_3") (pintype "bidirectional"))
    )
    (net (code "12") (name "EPD_BUSY") (class "Default")
      (node (ref "J1") (pin "9") (pinfunction "9_9") (pintype "bidirectional"))
      (node (ref "U1") (pin "P$AD12") (pinfunction "P0.17_P$AD12") (pintype "bidirectional"))
    )
    (net (code "13") (name "EPD_CS") (class "Default")
      (node (ref "J1") (pin "12") (pinfunction "12_12") (pintype "bidirectional"))
      (node (ref "U1") (pin "P$K2") (pinfunction "P0.05/AIN3_P$K2") (pintype "bidirectional"))
    )
    (net (code "14") (name "EPD_DC") (class "Default")
      (node (ref "J1") (pin "11") (pinfunction "11_11") (pintype "bidirectional"))
      (node (ref "U1") (pin "P$AD10") (pinfunction "P0.15_P$AD10") (pintype "bidirectional"))
    )
    (net (code "15") (name "EPD_RST") (class "Default")
      (node (ref "J1") (pin "10") (pinfunction "10_10") (pintype "bidirectional"))
      (node (ref "U1") (pin "P$AC11") (pinfunction "P0.16_P$AC11") (pintype "bidirectional"))
    )
    (net (code "16") (name "GDR") (class "Default")
      (node (ref "J1") (pin "2") (pinfunction "2_2") (pintype "bidirectional"))
      (node (ref "Q3") (pin "1") (pinfunction "G_1") (pintype "bidirectional"))
      (node (ref "R2-EP-DR") (pin "2") (pinfunction "2_2") (pintype "bidirectional"))
    )
    (net (code "17") (name "GND") (class "Default")
      (node (ref "C1") (pin "2") (pinfunction "2_2") (pintype "passive"))
      (node (ref "C1-EP-DR") (pin "2") (pinfunction "2_2") (pintype "passive"))
      (node (ref "C10") (pin "2") (pinfunction "2_2") (pintype "passive"))
      (node (ref "C11") (pin "2") (pinfunction "2_2") (pintype "passive"))
      (node (ref "C12") (pin "2") (pinfunction "2_2") (pintype "passive"))
      (node (ref "C13") (pin "2") (pinfunction "2_2") (pintype "passive"))
      (node (ref "C14") (pin "2") (pinfunction "2_2") (pintype "passive"))
      (node (ref "C15") (pin "2") (pinfunction "2_2") (pintype "passive"))
      (node (ref "C16") (pin "2") (pinfunction "2_2") (pintype "passive"))
      (node (ref "C17") (pin "1") (pinfunction "1_1") (pintype "passive"))
      (node (ref "C18") (pin "1") (pinfunction "1_1") (pintype "passive"))
      (node (ref "C19") (pin "2") (pinfunction "2_2") (pintype "passive"))
      (node (ref "C2") (pin "2") (pinfunction "2_2") (pintype "passive"))
      (node (ref "C20") (pin "2") (pinfunction "2_2") (pintype "passive"))
      (node (ref "C21") (pin "2") (pinfunction "2_2") (pintype "passive"))
      (node (ref "C22") (pin "2") (pinfunction "2_2") (pintype "passive"))
      (node (ref "C23") (pin "1") (pinfunction "1_1") (pintype "passive"))
      (node (ref "C24") (pin "1") (pinfunction "1_1") (pintype "passive"))
      (node (ref "C25") (pin "2") (pinfunction "2_2") (pintype "passive"))
      (node (ref "C27") (pin "1") (pinfunction "1_1") (pintype "passive"))
      (node (ref "C29") (pin "1") (pinfunction "1_1") (pintype "passive"))
      (node (ref "C3") (pin "2") (pinfunction "2_2") (pintype "passive"))
      (node (ref "C30") (pin "1") (pinfunction "1_1") (pintype "passive"))
      (node (ref "C31") (pin "1") (pinfunction "1_1") (pintype "passive"))
      (node (ref "C32") (pin "1") (pinfunction "1_1") (pintype "passive"))
      (node (ref "C33") (pin "2") (pinfunction "2_2") (pintype "passive"))
      (node (ref "C34") (pin "1") (pinfunction "1_1") (pintype "passive"))
      (node (ref "C37") (pin "2") (pinfunction "2_2") (pintype "passive"))
      (node (ref "C38") (pin "2") (pinfunction "2_2") (pintype "passive"))
      (node (ref "C39") (pin "2") (pinfunction "2_2") (pintype "passive"))
      (node (ref "C4") (pin "2") (pinfunction "2_2") (pintype "passive"))
      (node (ref "C42") (pin "2") (pinfunction "2_2") (pintype "passive"))
      (node (ref "C43") (pin "2") (pinfunction "2_2") (pintype "passive"))
      (node (ref "C5") (pin "2") (pinfunction "2_2") (pintype "passive"))
      (node (ref "C6") (pin "2") (pinfunction "2_2") (pintype "passive"))
      (node (ref "C7") (pin "2") (pinfunction "2_2") (pintype "passive"))
      (node (ref "C8") (pin "2") (pinfunction "2_2") (pintype "passive"))
      (node (ref "C9") (pin "2") (pinfunction "2_2") (pintype "passive"))
      (node (ref "D3") (pin "2") (pinfunction "GND_2") (pintype "bidirectional"))
      (node (ref "D4") (pin "1") (pinfunction "K_1") (pintype "bidirectional"))
      (node (ref "EPD_C1") (pin "1") (pinfunction "1_1") (pintype "passive"))
      (node (ref "EPD_C10") (pin "1") (pinfunction "1_1") (pintype "passive"))
      (node (ref "EPD_C11") (pin "1") (pinfunction "1_1") (pintype "passive"))
      (node (ref "EPD_C12") (pin "1") (pinfunction "1_1") (pintype "passive"))
      (node (ref "EPD_C2") (pin "1") (pinfunction "1_1") (pintype "passive"))
      (node (ref "EPD_C5") (pin "1") (pinfunction "1_1") (pintype "passive"))
      (node (ref "EPD_C6") (pin "1") (pinfunction "1_1") (pintype "passive"))
      (node (ref "EPD_C7") (pin "1") (pinfunction "1_1") (pintype "passive"))
      (node (ref "EPD_C8") (pin "1") (pinfunction "1_1") (pintype "passive"))
      (node (ref "EPD_C9") (pin "1") (pinfunction "1_1") (pintype "passive"))
      (node (ref "IC1") (pin "D2") (pinfunction "GND_D2") (pintype "bidirectional"))
      (node (ref "IC2") (pin "B1") (pinfunction "IN/TRIG_B1") (pintype "bidirectional"))
      (node (ref "IC2") (pin "B3") (pinfunction "GND_B3") (pintype "bidirectional"))
      (node (ref "IC3") (pin "8") (pinfunction "GNDIO_8") (pintype "bidirectional"))
      (node (ref "IC3") (pin "9") (pinfunction "GND_9") (pintype "bidirectional"))
      (node (ref "IC9") (pin "B1") (pinfunction "VSEL_B1") (pintype "bidirectional"))
      (node (ref "IC9") (pin "C1") (pinfunction "AGND_C1") (pintype "bidirectional"))
      (node (ref "IC9") (pin "C2") (pinfunction "PGND_1_C2") (pintype "bidirectional"))
      (node (ref "IC9") (pin "C3") (pinfunction "PGND_2_C3") (pintype "bidirectional"))
      (node (ref "J1") (pin "17") (pinfunction "17_17") (pintype "bidirectional"))
      (node (ref "J1") (pin "8") (pinfunction "8_8") (pintype "bidirectional"))
      (node (ref "J1") (pin "MP1") (pinfunction "MP1_MP1") (pintype "bidirectional"))
      (node (ref "J1") (pin "MP2") (pinfunction "MP2_MP2") (pintype "bidirectional"))
      (node (ref "J2") (pin "3") (pinfunction "3_3") (pintype "bidirectional"))
      (node (ref "J2") (pin "5") (pinfunction "5_5") (pintype "bidirectional"))
      (node (ref "J4") (pin "A12_B1") (pinfunction "GND_A12_B1") (pintype "power_in"))
      (node (ref "J4") (pin "A1_B12") (pinfunction "GND_A1_B12") (pintype "power_in"))
      (node (ref "J4") (pin "SH1") (pinfunction "SHIELD_SH1") (pintype "passive"))
      (node (ref "J4") (pin "SH2") (pinfunction "SHIELD_SH2") (pintype "passive"))
      (node (ref "J4") (pin "SH3") (pinfunction "SHIELD_SH3") (pintype "passive"))
      (node (ref "J4") (pin "SH4") (pinfunction "SHIELD_SH4") (pintype "passive"))
      (node (ref "R1_USB") (pin "1") (pinfunction "1_1") (pintype "bidirectional"))
      (node (ref "R2-EP-DR") (pin "1") (pinfunction "1_1") (pintype "bidirectional"))
      (node (ref "R2_USB") (pin "2") (pinfunction "2_2") (pintype "bidirectional"))
      (node (ref "R3") (pin "1") (pinfunction "1_1") (pintype "bidirectional"))
      (node (ref "R9") (pin "1") (pinfunction "1_1") (pintype "bidirectional"))
      (node (ref "R_TYPE_SEL") (pin "1") (pinfunction "1_1") (pintype "bidirectional"))
      (node (ref "SJ1") (pin "1") (pinfunction "1_1") (pintype "passive"))
      (node (ref "SW_DN") (pin "1") (pinfunction "1_1") (pintype "passive"))
      (node (ref "SW_ENT") (pin "1") (pinfunction "1_1") (pintype "passive"))
      (node (ref "SW_UP") (pin "1") (pinfunction "1_1") (pintype "passive"))
      (node (ref "TP_BAT_GND") (pin "TP") (pinfunction "TP_TP") (pintype "input"))
      (node (ref "TP_GND") (pin "TP") (pinfunction "TP_TP") (pintype "input"))
      (node (ref "U1") (pin "P$74") (pinfunction "VSS_PAD_P$74") (pintype "bidirectional"))
      (node (ref "U1") (pin "P$75") (pinfunction "VSS_PAD_P$75") (pintype "bidirectional"))
      (node (ref "U1") (pin "P$76") (pinfunction "VSS_PAD_P$76") (pintype "bidirectional"))
      (node (ref "U1") (pin "P$77") (pinfunction "VSS_PAD_P$77") (pintype "bidirectional"))
      (node (ref "U1") (pin "P$78") (pinfunction "VSS_PAD_P$78") (pintype "bidirectional"))
      (node (ref "U1") (pin "P$79") (pinfunction "VSS_PAD_P$79") (pintype "bidirectional"))
      (node (ref "U1") (pin "P$80") (pinfunction "VSS_PAD_P$80") (pintype "bidirectional"))
      (node (ref "U1") (pin "P$81") (pinfunction "VSS_PAD_P$81") (pintype "bidirectional"))
      (node (ref "U1") (pin "P$82") (pinfunction "VSS_PAD_P$82") (pintype "bidirectional"))
      (node (ref "U1") (pin "P$83") (pinfunction "VSS_PAD_P$83") (pintype "bidirectional"))
      (node (ref "U1") (pin "P$84") (pinfunction "VSS_PAD_P$84") (pintype "bidirectional"))
      (node (ref "U1") (pin "P$85") (pinfunction "VSS_PAD_P$85") (pintype "bidirectional"))
      (node (ref "U1") (pin "P$86") (pinfunction "VSS_PAD_P$86") (pintype "bidirectional"))
      (node (ref "U1") (pin "P$87") (pinfunction "VSS_PAD_P$87") (pintype "bidirectional"))
      (node (ref "U1") (pin "P$88") (pinfunction "VSS_PAD_P$88") (pintype "bidirectional"))
      (node (ref "U1") (pin "P$89") (pinfunction "VSS_PAD_P$89") (pintype "bidirectional"))
      (node (ref "U1") (pin "P$90") (pinfunction "VSS_PAD_P$90") (pintype "bidirectional"))
      (node (ref "U1") (pin "P$B7") (pinfunction "VSS_P$B7") (pintype "power_in"))
      (node (ref "U1") (pin "P$F23") (pinfunction "VSS_PA_P$F23") (pintype "bidirectional"))
      (node (ref "U3") (pin "1") (pinfunction "CTG_1") (pintype "power_in"))
      (node (ref "U3") (pin "4") (pinfunction "GND_4") (pintype "power_in"))
      (node (ref "U3") (pin "6") (pinfunction "QSTRT_6") (pintype "input"))
      (node (ref "U3") (pin "9") (pinfunction "EP_9") (pintype "power_in"))
      (node (ref "X1") (pin "2") (pinfunction "2_2") (pintype "passive"))
      (node (ref "X1") (pin "4") (pinfunction "4_4") (pintype "passive"))
    )
    (net (code "18") (name "HAPTIC_EN") (class "Default")
      (node (ref "IC2") (pin "A1") (pinfunction "EN_A1") (pintype "bidirectional"))
      (node (ref "U1") (pin "P$U1") (pinfunction "P0.12_P$U1") (pintype "bidirectional"))
    )
    (net (code "19") (name "IMU_INT1") (class "Default")
      (node (ref "IC3") (pin "5") (pinfunction "INT1_5") (pintype "bidirectional"))
      (node (ref "U1") (pin "P$N1") (pinfunction "P0.08_P$N1") (pintype "bidirectional"))
    )
    (net (code "20") (name "IMU_INT2") (class "Default")
      (node (ref "IC3") (pin "6") (pinfunction "INT2_6") (pintype "bidirectional"))
      (node (ref "U1") (pin "P$P2") (pinfunction "P1.08_P$P2") (pintype "bidirectional"))
    )
    (net (code "21") (name "LX1") (class "Default")
      (node (ref "IC9") (pin "B2") (pinfunction "SW1_1_B2") (pintype "bidirectional"))
      (node (ref "IC9") (pin "B3") (pinfunction "SW1_2_B3") (pintype "bidirectional"))
      (node (ref "L7") (pin "1") (pinfunction "1_1") (pintype "bidirectional"))
    )
    (net (code "22") (name "LX2") (class "Default")
      (node (ref "IC9") (pin "D2") (pinfunction "SW2_1_D2") (pintype "bidirectional"))
      (node (ref "IC9") (pin "D3") (pinfunction "SW2_2_D3") (pintype "bidirectional"))
      (node (ref "L7") (pin "2") (pinfunction "2_2") (pintype "bidirectional"))
    )
    (net (code "23") (name "MOSI") (class "Default")
      (node (ref "J1") (pin "14") (pinfunction "14_14") (pintype "bidirectional"))
      (node (ref "U1") (pin "P$B13") (pinfunction "P0.03/AIN1_P$B13") (pintype "bidirectional"))
    )
    (net (code "24") (name "Net-(D2-K)") (class "Default")
      (node (ref "C2-EP-DR") (pin "1") (pinfunction "1_1") (pintype "passive"))
      (node (ref "D2") (pin "1") (pinfunction "K_1") (pintype "bidirectional"))
      (node (ref "D4") (pin "2") (pinfunction "A_2") (pintype "bidirectional"))
    )
    (net (code "25") (name "Net-(D5-A)") (class "Default")
      (node (ref "C2-EP-DR") (pin "2") (pinfunction "2_2") (pintype "passive"))
      (node (ref "D5") (pin "2") (pinfunction "A_2") (pintype "bidirectional"))
      (node (ref "L5") (pin "1") (pinfunction "1_1") (pintype "passive"))
      (node (ref "Q3") (pin "3") (pinfunction "D_3") (pintype "bidirectional"))
    )
    (net (code "26") (name "Net-(EPD_C1-Pad2)") (class "Default")
      (node (ref "EPD_C1") (pin "2") (pinfunction "2_2") (pintype "passive"))
      (node (ref "J1") (pin "5") (pinfunction "5_5") (pintype "bidirectional"))
    )
    (net (code "27") (name "Net-(EPD_C2-Pad2)") (class "Default")
      (node (ref "EPD_C2") (pin "2") (pinfunction "2_2") (pintype "passive"))
      (node (ref "J1") (pin "4") (pinfunction "4_4") (pintype "bidirectional"))
    )
    (net (code "28") (name "Net-(EPD_C6-Pad2)") (class "Default")
      (node (ref "EPD_C6") (pin "2") (pinfunction "2_2") (pintype "passive"))
      (node (ref "J1") (pin "18") (pinfunction "18_18") (pintype "bidirectional"))
    )
    (net (code "29") (name "Net-(EPD_C7-Pad2)") (class "Default")
      (node (ref "EPD_C7") (pin "2") (pinfunction "2_2") (pintype "passive"))
      (node (ref "J1") (pin "19") (pinfunction "19_19") (pintype "bidirectional"))
    )
    (net (code "30") (name "Net-(EPD_C8-Pad2)") (class "Default")
      (node (ref "EPD_C8") (pin "2") (pinfunction "2_2") (pintype "passive"))
      (node (ref "J1") (pin "20") (pinfunction "20_20") (pintype "bidirectional"))
    )
    (net (code "31") (name "Net-(EPD_C10-Pad2)") (class "Default")
      (node (ref "EPD_C10") (pin "2") (pinfunction "2_2") (pintype "passive"))
      (node (ref "J1") (pin "22") (pinfunction "22_22") (pintype "bidirectional"))
    )
    (net (code "32") (name "Net-(EPD_C12-Pad2)") (class "Default")
      (node (ref "EPD_C12") (pin "2") (pinfunction "2_2") (pintype "passive"))
      (node (ref "J1") (pin "24") (pinfunction "24_24") (pintype "bidirectional"))
    )
    (net (code "33") (name "Net-(IC1-TS{slash}MR)") (class "Default")
      (node (ref "IC1") (pin "D1") (pinfunction "TS/MR_D1") (pintype "bidirectional"))
      (node (ref "R9") (pin "2") (pinfunction "2_2") (pintype "bidirectional"))
    )
    (net (code "34") (name "Net-(IC2-REG)") (class "Default")
      (node (ref "C32") (pin "2") (pinfunction "2_2") (pintype "passive"))
      (node (ref "IC2") (pin "A2") (pinfunction "REG_A2") (pintype "bidirectional"))
    )
    (net (code "35") (name "Net-(IC3-SDO)") (class "Default")
      (node (ref "IC3") (pin "1") (pinfunction "SDO_1") (pintype "bidirectional"))
      (node (ref "R3") (pin "2") (pinfunction "2_2") (pintype "bidirectional"))
    )
    (net (code "36") (name "Net-(IC9-SCL)") (class "Default")
      (node (ref "IC9") (pin "D1") (pinfunction "SCL_D1") (pintype "bidirectional"))
      (node (ref "R4") (pin "2") (pinfunction "2_2") (pintype "bidirectional"))
    )
    (net (code "37") (name "Net-(IC9-SDA)") (class "Default")
      (node (ref "IC9") (pin "E1") (pinfunction "SDA_E1") (pintype "bidirectional"))
      (node (ref "R2") (pin "2") (pinfunction "2_2") (pintype "bidirectional"))
    )
    (net (code "38") (name "Net-(J4-CC1)") (class "Default")
      (node (ref "J4") (pin "A5") (pinfunction "CC1_A5") (pintype "bidirectional"))
      (node (ref "R1_USB") (pin "2") (pinfunction "2_2") (pintype "bidirectional"))
    )
    (net (code "39") (name "Net-(J4-CC2)") (class "Default")
      (node (ref "J4") (pin "B5") (pinfunction "CC2_B5") (pintype "bidirectional"))
      (node (ref "R2_USB") (pin "1") (pinfunction "1_1") (pintype "bidirectional"))
    )
    (net (code "40") (name "Net-(L2-Pad2)") (class "Default")
      (node (ref "L2") (pin "2") (pinfunction "2_2") (pintype "passive"))
      (node (ref "L3") (pin "1") (pinfunction "1_1") (pintype "passive"))
    )
    (net (code "41") (name "Net-(R1-EP-DR-Pad1)") (class "Default")
      (node (ref "R1-EP-DR") (pin "1") (pinfunction "1_1") (pintype "bidirectional"))
      (node (ref "R_TYPE_SEL") (pin "2") (pinfunction "2_2") (pintype "bidirectional"))
      (node (ref "SJ1") (pin "2") (pinfunction "2_2") (pintype "passive"))
    )
    (net (code "42") (name "Net-(U1-ANT)") (class "Default")
      (node (ref "C3") (pin "1") (pinfunction "1_1") (pintype "passive"))
      (node (ref "L1") (pin "1") (pinfunction "1_1") (pintype "passive"))
      (node (ref "U1") (pin "P$H23") (pinfunction "ANT_P$H23") (pintype "bidirectional"))
    )
    (net (code "43") (name "Net-(U1-DCC)") (class "Default")
      (node (ref "L2") (pin "1") (pinfunction "1_1") (pintype "passive"))
      (node (ref "U1") (pin "P$B3") (pinfunction "DCC_P$B3") (pintype "output"))
    )
    (net (code "44") (name "Net-(U1-DEC2)") (class "Default")
      (node (ref "C13") (pin "1") (pinfunction "1_1") (pintype "passive"))
      (node (ref "U1") (pin "P$A18") (pinfunction "DEC2_P$A18") (pintype "bidirectional"))
    )
    (net (code "45") (name "Net-(U1-DEC3V3)") (class "Default")
      (node (ref "C20") (pin "1") (pinfunction "1_1") (pintype "passive"))
      (node (ref "U1") (pin "P$AC5") (pinfunction "DEC3V3_P$AC5") (pintype "bidirectional"))
    )
    (net (code "46") (name "Net-(U1-DEC5)") (class "Default")
      (node (ref "C9") (pin "1") (pinfunction "1_1") (pintype "passive"))
      (node (ref "U1") (pin "P$N24") (pinfunction "DEC5_P$N24") (pintype "bidirectional"))
    )
    (net (code "47") (name "Net-(U1-P0.00{slash}XL1)") (class "Default")
      (node (ref "C18") (pin "2") (pinfunction "2_2") (pintype "passive"))
      (node (ref "U1") (pin "P$D2") (pinfunction "P0.00/XL1_P$D2") (pintype "bidirectional"))
      (node (ref "X2") (pin "2") (pinfunction "2_2") (pintype "passive"))
    )
    (net (code "48") (name "Net-(U1-P0.01{slash}XL2)") (class "Default")
      (node (ref "C17") (pin "2") (pinfunction "2_2") (pintype "passive"))
      (node (ref "U1") (pin "P$F2") (pinfunction "P0.01/XL2_P$F2") (pintype "bidirectional"))
      (node (ref "X2") (pin "1") (pinfunction "1_1") (pintype "passive"))
    )
    (net (code "49") (name "Net-(U1-XC1)") (class "Default")
      (node (ref "C1") (pin "1") (pinfunction "1_1") (pintype "passive"))
      (node (ref "U1") (pin "P$B24") (pinfunction "XC1_P$B24") (pintype "input"))
      (node (ref "X1") (pin "1") (pinfunction "1_1") (pintype "passive"))
    )
    (net (code "50") (name "Net-(U1-XC2)") (class "Default")
      (node (ref "C2") (pin "1") (pinfunction "1_1") (pintype "passive"))
      (node (ref "U1") (pin "P$A23") (pinfunction "XC2_P$A23") (pintype "output"))
      (node (ref "X1") (pin "3") (pinfunction "3_3") (pintype "passive"))
    )
    (net (code "51") (name "OUT+") (class "Default")
      (node (ref "IC2") (pin "A3") (pinfunction "OUT+_A3") (pintype "bidirectional"))
      (node (ref "TP1") (pin "TP") (pinfunction "TP_TP") (pintype "input"))
    )
    (net (code "52") (name "OUT-") (class "Default")
      (node (ref "IC2") (pin "C3") (pinfunction "OUT-_C3") (pintype "bidirectional"))
      (node (ref "TP2") (pin "TP") (pinfunction "TP_TP") (pintype "input"))
    )
    (net (code "53") (name "P0.04") (class "Default")
      (node (ref "U1") (pin "P$J1") (pinfunction "P0.04/AIN2_P$J1") (pintype "bidirectional"))
    )
    (net (code "54") (name "P0.09") (class "Default")
      (node (ref "U1") (pin "P$L24") (pinfunction "P0.09/NFC1_P$L24") (pintype "bidirectional"))
    )
    (net (code "55") (name "P0.13") (class "Default")
      (node (ref "C30") (pin "2") (pinfunction "2_2") (pintype "passive"))
      (node (ref "R5") (pin "1") (pinfunction "1_1") (pintype "bidirectional"))
      (node (ref "SW_UP") (pin "2") (pinfunction "2_2") (pintype "passive"))
      (node (ref "U1") (pin "P$AD8") (pinfunction "P0.13_P$AD8") (pintype "bidirectional"))
    )
    (net (code "56") (name "P0.14") (class "Default")
      (node (ref "C31") (pin "2") (pinfunction "2_2") (pintype "passive"))
      (node (ref "R8") (pin "1") (pinfunction "1_1") (pintype "bidirectional"))
      (node (ref "SW_ENT") (pin "2") (pinfunction "2_2") (pintype "passive"))
      (node (ref "U1") (pin "P$AC9") (pinfunction "P0.14_P$AC9") (pintype "bidirectional"))
    )
    (net (code "57") (name "P0.19") (class "Default")
      (node (ref "U1") (pin "P$AC15") (pinfunction "P0.19_P$AC15") (pintype "bidirectional"))
    )
    (net (code "58") (name "P0.20") (class "Default")
      (node (ref "U1") (pin "P$AD16") (pinfunction "P0.20_P$AD16") (pintype "bidirectional"))
    )
    (net (code "59") (name "P0.21") (class "Default")
      (node (ref "U1") (pin "P$AC17") (pinfunction "P0.21_P$AC17") (pintype "bidirectional"))
    )
    (net (code "60") (name "P0.22") (class "Default")
      (node (ref "U1") (pin "P$AD18") (pinfunction "P0.22_P$AD18") (pintype "bidirectional"))
    )
    (net (code "61") (name "P0.23") (class "Default")
      (node (ref "U1") (pin "P$AC19") (pinfunction "P0.23_P$AC19") (pintype "bidirectional"))
    )
    (net (code "62") (name "P0.24") (class "Default")
      (node (ref "U1") (pin "P$AD20") (pinfunction "P0.24_P$AD20") (pintype "bidirectional"))
    )
    (net (code "63") (name "P0.25") (class "Default")
      (node (ref "U1") (pin "P$AC21") (pinfunction "P0.25_P$AC21") (pintype "bidirectional"))
    )
    (net (code "64") (name "P0.26") (class "Default")
      (node (ref "U1") (pin "P$G1") (pinfunction "P0.26_P$G1") (pintype "bidirectional"))
    )
    (net (code "65") (name "P0.27") (class "Default")
      (node (ref "U1") (pin "P$H2") (pinfunction "P0.27_P$H2") (pintype "bidirectional"))
    )
    (net (code "66") (name "P0.28") (class "Default")
      (node (ref "U1") (pin "P$B11") (pinfunction "P0.28/AIN4_P$B11") (pintype "bidirectional"))
    )
    (net (code "67") (name "P0.29") (class "Default")
      (node (ref "U1") (pin "P$A10") (pinfunction "P0.29/AIN5_P$A10") (pintype "bidirectional"))
    )
    (net (code "68") (name "P0.30") (class "Default")
      (node (ref "U1") (pin "P$B9") (pinfunction "P0.30/AIN6_P$B9") (pintype "bidirectional"))
    )
    (net (code "69") (name "P0.31") (class "Default")
      (node (ref "U1") (pin "P$A8") (pinfunction "P0.31/AIN7_P$A8") (pintype "bidirectional"))
    )
    (net (code "70") (name "P1.01") (class "Default")
      (node (ref "Q1") (pin "1") (pinfunction "G_1") (pintype "bidirectional"))
      (node (ref "R_PWR_EPD") (pin "1") (pinfunction "1_1") (pintype "bidirectional"))
      (node (ref "U1") (pin "P$Y23") (pinfunction "P1.01_P$Y23") (pintype "bidirectional"))
    )
    (net (code "71") (name "P1.02") (class "Default")
      (node (ref "C29") (pin "2") (pinfunction "2_2") (pintype "passive"))
      (node (ref "R7") (pin "1") (pinfunction "1_1") (pintype "bidirectional"))
      (node (ref "SW_DN") (pin "2") (pinfunction "2_2") (pintype "passive"))
      (node (ref "U1") (pin "P$W24") (pinfunction "P1.02_P$W24") (pintype "bidirectional"))
    )
    (net (code "72") (name "P1.03") (class "Default")
      (node (ref "U1") (pin "P$V23") (pinfunction "P1.03_P$V23") (pintype "bidirectional"))
    )
    (net (code "73") (name "P1.04") (class "Default")
      (node (ref "U1") (pin "P$U24") (pinfunction "P1.04_P$U24") (pintype "bidirectional"))
    )
    (net (code "74") (name "P1.05") (class "Default")
      (node (ref "U1") (pin "P$T23") (pinfunction "P1.05_P$T23") (pintype "bidirectional"))
    )
    (net (code "75") (name "P1.06") (class "Default")
      (node (ref "U1") (pin "P$R24") (pinfunction "P1.06_P$R24") (pintype "bidirectional"))
    )
    (net (code "76") (name "P1.07") (class "Default")
      (node (ref "U1") (pin "P$P23") (pinfunction "P1.07_P$P23") (pintype "bidirectional"))
    )
    (net (code "77") (name "P1.09") (class "Default")
      (node (ref "U1") (pin "P$R1") (pinfunction "P1.09_P$R1") (pintype "bidirectional"))
    )
    (net (code "78") (name "P1.10") (class "Default")
      (node (ref "U1") (pin "P$A20") (pinfunction "P1.10_P$A20") (pintype "bidirectional"))
    )
    (net (code "79") (name "P1.11") (class "Default")
      (node (ref "U1") (pin "P$B19") (pinfunction "P1.11_P$B19") (pintype "bidirectional"))
    )
    (net (code "80") (name "P1.12") (class "Default")
      (node (ref "U1") (pin "P$B17") (pinfunction "P1.12_P$B17") (pintype "bidirectional"))
    )
    (net (code "81") (name "P1.13") (class "Default")
      (node (ref "U1") (pin "P$A16") (pinfunction "P1.13_P$A16") (pintype "bidirectional"))
    )
    (net (code "82") (name "P1.14") (class "Default")
      (node (ref "U1") (pin "P$B15") (pinfunction "P1.14_P$B15") (pintype "bidirectional"))
    )
    (net (code "83") (name "P1.15") (class "Default")
      (node (ref "U1") (pin "P$A14") (pinfunction "P1.15_P$A14") (pintype "bidirectional"))
    )
    (net (code "84") (name "PMIC_INT") (class "Default")
      (node (ref "IC1") (pin "A1") (pinfunction "~{INT}_A1") (pintype "bidirectional"))
      (node (ref "U1") (pin "P$T2") (pinfunction "P0.11_P$T2") (pintype "bidirectional"))
    )
    (net (code "85") (name "PREVGH") (class "Default")
      (node (ref "D5") (pin "1") (pinfunction "K_1") (pintype "bidirectional"))
      (node (ref "EPD_C9") (pin "2") (pinfunction "2_2") (pintype "passive"))
      (node (ref "J1") (pin "21") (pinfunction "21_21") (pintype "bidirectional"))
    )
    (net (code "86") (name "PREVGL") (class "Default")
      (node (ref "D2") (pin "2") (pinfunction "A_2") (pintype "bidirectional"))
      (node (ref "EPD_C11") (pin "2") (pinfunction "2_2") (pintype "passive"))
      (node (ref "J1") (pin "23") (pinfunction "23_23") (pintype "bidirectional"))
    )
    (net (code "87") (name "RESE") (class "Default")
      (node (ref "J1") (pin "3") (pinfunction "3_3") (pintype "bidirectional"))
      (node (ref "Q3") (pin "2") (pinfunction "S_2") (pintype "bidirectional"))
      (node (ref "R1-EP-DR") (pin "2") (pinfunction "2_2") (pintype "bidirectional"))
    )
    (net (code "88") (name "RESET") (class "Default")
      (node (ref "J2") (pin "6") (pinfunction "6_6") (pintype "bidirectional"))
      (node (ref "TP_RESET") (pin "TP") (pinfunction "TP_TP") (pintype "input"))
      (node (ref "U1") (pin "P$AC13") (pinfunction "P0.18/RESET_P$AC13") (pintype "bidirectional"))
    )
    (net (code "89") (name "RF") (class "Default")
      (node (ref "ANT1") (pin "1") (pinfunction "FEED_1") (pintype "input"))
      (node (ref "C22") (pin "1") (pinfunction "1_1") (pintype "passive"))
      (node (ref "C4") (pin "1") (pinfunction "1_1") (pintype "passive"))
      (node (ref "L1") (pin "2") (pinfunction "2_2") (pintype "passive"))
    )
    (net (code "90") (name "SCK") (class "Default")
      (node (ref "J1") (pin "13") (pinfunction "13_13") (pintype "bidirectional"))
      (node (ref "U1") (pin "P$A12") (pinfunction "P0.02/AIN0_P$A12") (pintype "bidirectional"))
    )
    (net (code "91") (name "SCL") (class "Default")
      (node (ref "IC1") (pin "B1") (pinfunction "SCL_B1") (pintype "bidirectional"))
      (node (ref "IC2") (pin "C1") (pinfunction "SCL_C1") (pintype "bidirectional"))
      (node (ref "IC3") (pin "12") (pinfunction "SCX_12") (pintype "bidirectional"))
      (node (ref "R17") (pin "2") (pinfunction "2_2") (pintype "bidirectional"))
      (node (ref "R4") (pin "1") (pinfunction "1_1") (pintype "bidirectional"))
      (node (ref "TP_SCL") (pin "TP") (pinfunction "TP_TP") (pintype "input"))
      (node (ref "U1") (pin "P$M2") (pinfunction "P0.07_P$M2") (pintype "bidirectional"))
      (node (ref "U3") (pin "7") (pinfunction "SCL_7") (pintype "input"))
    )
    (net (code "92") (name "SDA") (class "Default")
      (node (ref "IC1") (pin "C1") (pinfunction "SDA_C1") (pintype "bidirectional"))
      (node (ref "IC2") (pin "B2") (pinfunction "SDA_B2") (pintype "bidirectional"))
      (node (ref "IC3") (pin "2") (pinfunction "SDX_2") (pintype "bidirectional"))
      (node (ref "R18") (pin "2") (pinfunction "2_2") (pintype "bidirectional"))
      (node (ref "R2") (pin "1") (pinfunction "1_1") (pintype "bidirectional"))
      (node (ref "TP_SDA") (pin "TP") (pinfunction "TP_TP") (pintype "input"))
      (node (ref "U1") (pin "P$L1") (pinfunction "P0.06_P$L1") (pintype "bidirectional"))
      (node (ref "U3") (pin "8") (pinfunction "SDA_8") (pintype "bidirectional"))
    )
    (net (code "93") (name "SWDCLK") (class "Default")
      (node (ref "J2") (pin "4") (pinfunction "4_4") (pintype "bidirectional"))
      (node (ref "TP_SWDCLK") (pin "TP") (pinfunction "TP_TP") (pintype "input"))
      (node (ref "U1") (pin "P$AA24") (pinfunction "SWDCLK_P$AA24") (pintype "input"))
    )
    (net (code "94") (name "SWDIO") (class "Default")
      (node (ref "J2") (pin "2") (pinfunction "2_2") (pintype "bidirectional"))
      (node (ref "TP_SWDIO") (pin "TP") (pinfunction "TP_TP") (pintype "input"))
      (node (ref "U1") (pin "P$AC24") (pinfunction "SWDIO_P$AC24") (pintype "bidirectional"))
    )
    (net (code "95") (name "SWO") (class "Default")
      (node (ref "TP_SWO") (pin "TP") (pinfunction "TP_TP") (pintype "input"))
      (node (ref "U1") (pin "P$AD22") (pinfunction "P1.00_P$AD22") (pintype "bidirectional"))
    )
    (net (code "96") (name "VBAT") (class "Default")
      (node (ref "C27") (pin "2") (pinfunction "2_2") (pintype "passive"))
      (node (ref "C37") (pin "1") (pinfunction "1_1") (pintype "passive"))
      (node (ref "IC1") (pin "C2") (pinfunction "BAT_C2") (pintype "bidirectional"))
      (node (ref "TP_VBAT") (pin "TP") (pinfunction "TP_TP") (pintype "input"))
      (node (ref "U3") (pin "2") (pinfunction "CELL_2") (pintype "power_in"))
      (node (ref "U3") (pin "3") (pinfunction "VDD_3") (pintype "power_in"))
    )
    (net (code "97") (name "VBUS") (class "Default")
      (node (ref "C21") (pin "1") (pinfunction "1_1") (pintype "passive"))
      (node (ref "C38") (pin "1") (pinfunction "1_1") (pintype "passive"))
      (node (ref "C42") (pin "1") (pinfunction "1_1") (pintype "passive"))
      (node (ref "C43") (pin "1") (pinfunction "1_1") (pintype "passive"))
      (node (ref "D3") (pin "5") (pinfunction "VBUS_5") (pintype "bidirectional"))
      (node (ref "IC1") (pin "A2") (pinfunction "IN_A2") (pintype "bidirectional"))
      (node (ref "J4") (pin "A4_B9") (pinfunction "VBUS_A4_B9") (pintype "power_in"))
      (node (ref "J4") (pin "A9_B4") (pinfunction "VBUS_A9_B4") (pintype "power_in"))
      (node (ref "U1") (pin "P$AD2") (pinfunction "VBUS_P$AD2") (pintype "power_in"))
    )
    (net (code "98") (name "VREG") (class "Default")
      (node (ref "C23") (pin "2") (pinfunction "2_2") (pintype "passive"))
      (node (ref "C24") (pin "2") (pinfunction "2_2") (pintype "passive"))
      (node (ref "C39") (pin "1") (pinfunction "1_1") (pintype "passive"))
      (node (ref "IC1") (pin "B2") (pinfunction "SYS_B2") (pintype "bidirectional"))
      (node (ref "IC9") (pin "A1") (pinfunction "EN_A1") (pintype "bidirectional"))
      (node (ref "IC9") (pin "A2") (pinfunction "VIN_1_A2") (pintype "bidirectional"))
      (node (ref "IC9") (pin "A3") (pinfunction "VIN_2_A3") (pintype "bidirectional"))
      (node (ref "TP_VREG") (pin "TP") (pinfunction "TP_TP") (pintype "input"))
    )
    (net (code "99") (name "unconnected-(ANT1-NC-Pad2)") (class "Default")
      (node (ref "ANT1") (pin "2") (pinfunction "NC_2") (pintype "no_connect"))
    )
    (net (code "100") (name "unconnected-(IC3-ASCL-Pad11)") (class "Default")
      (node (ref "IC3") (pin "11") (pinfunction "ASCL_11") (pintype "bidirectional"))
    )
    (net (code "101") (name "unconnected-(IC3-ASDA-Pad4)") (class "Default")
      (node (ref "IC3") (pin "4") (pinfunction "ASDA_4") (pintype "bidirectional"))
    )
    (net (code "102") (name "unconnected-(J1-Pad1)") (class "Default")
      (node (ref "J1") (pin "1") (pinfunction "1_1") (pintype "bidirectional"))
    )
    (net (code "103") (name "unconnected-(J1-Pad6)") (class "Default")
      (node (ref "J1") (pin "6") (pinfunction "6_6") (pintype "bidirectional"))
    )
    (net (code "104") (name "unconnected-(J1-Pad7)") (class "Default")
      (node (ref "J1") (pin "7") (pinfunction "7_7") (pintype "bidirectional"))
    )
    (net (code "105") (name "unconnected-(J4-SBU1-PadA8)") (class "Default")
      (node (ref "J4") (pin "A8") (pinfunction "SBU1_A8") (pintype "bidirectional"))
    )
    (net (code "106") (name "unconnected-(J4-SBU2-PadB8)") (class "Default")
      (node (ref "J4") (pin "B8") (pinfunction "SBU2_B8") (pintype "bidirectional"))
    )
    (net (code "107") (name "unconnected-(U1-DCCH-PadP$AB2)") (class "Default")
      (node (ref "U1") (pin "P$AB2") (pinfunction "DCCH_P$AB2") (pintype "bidirectional"))
    )
  )
)
